# LED.net
KiCad netlist of a schematic drawn in Altium Designer
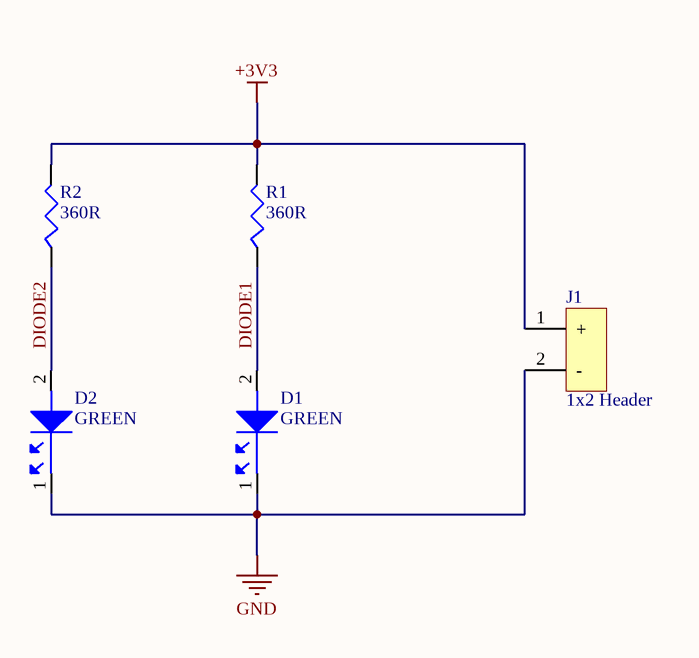
[diagram p0: LED.SchDoc]

(export (version "E")
  (design (tool "Eeschema 10.0.6"))
  (components
    (comp (ref "D1")
      (value "GREEN")
      (footprint "LED0603G")
      (description "LED GREEN CLEAR CHIP 0603 SMD")
      (fields (field (name "MANUFACTURER") "VCC") (field (name "MANUFACTURER PART NUMBER") "LSM0603453V"))
      (libsource (lib "LED") (part "LSM0603453V"))
    )
    (comp (ref "D2")
      (value "GREEN")
      (footprint "LED0603G")
      (description "LED GREEN CLEAR CHIP 0603 SMD")
      (fields (field (name "MANUFACTURER") "VCC") (field (name "MANUFACTURER PART NUMBER") "LSM0603453V"))
      (libsource (lib "LED") (part "LSM0603453V"))
    )
    (comp (ref "J1")
      (value "1x2 Header")
      (footprint "HDR1X2")
      (description "CONN HEADER VERT 2POS 2.54MM")
      (fields (field (name "MANUFACTURER") "Molex") (field (name "MANUFACTURER PART NUMBER") "22-27-2021"))
      (libsource (lib "LED") (part "22-27-2021"))
    )
    (comp (ref "R1")
      (value "360R")
      (footprint "R0805")
      (description "RES SMD 360 OHM 1% 1/8W 0805")
      (fields
        (field (name "MANUFACTURER") "Yageo Group")
        (field (name "MANUFACTURER PART NUMBER") "AC0805FR-07360RL")
      )
      (libsource (lib "LED") (part "AC0805FR-07360RL"))
    )
    (comp (ref "R2")
      (value "360R")
      (footprint "R0805")
      (description "RES SMD 360 OHM 1% 1/8W 0805")
      (fields
        (field (name "MANUFACTURER") "Yageo Group")
        (field (name "MANUFACTURER PART NUMBER") "AC0805FR-07360RL")
      )
      (libsource (lib "LED") (part "AC0805FR-07360RL"))
    )
  )
  (nets
    (net (code "1") (name "+3V3") (class "Default")
      (node (ref "J1") (pin "1") (pinfunction "+_1") (pintype "passive"))
      (node (ref "R1") (pin "2") (pinfunction "2_2") (pintype "passive"))
      (node (ref "R2") (pin "2") (pinfunction "2_2") (pintype "passive"))
    )
    (net (code "2") (name "/DIODE1") (class "Default")
      (node (ref "D1") (pin "2") (pinfunction "2_2") (pintype "passive"))
      (node (ref "R1") (pin "1") (pinfunction "1_1") (pintype "passive"))
    )
    (net (code "3") (name "/DIODE2") (class "Default")
      (node (ref "D2") (pin "2") (pinfunction "2_2") (pintype "passive"))
      (node (ref "R2") (pin "1") (pinfunction "1_1") (pintype "passive"))
    )
    (net (code "4") (name "GND") (class "Default")
      (node (ref "D1") (pin "1") (pinfunction "1_1") (pintype "passive"))
      (node (ref "D2") (pin "1") (pinfunction "1_1") (pintype "passive"))
      (node (ref "J1") (pin "2") (pinfunction "-_2") (pintype "passive"))
    )
  )
)
